# ProProject_New_Project_2023-08-26_19-08-.net
KiCad netlist of a schematic drawn in EasyEDA Pro
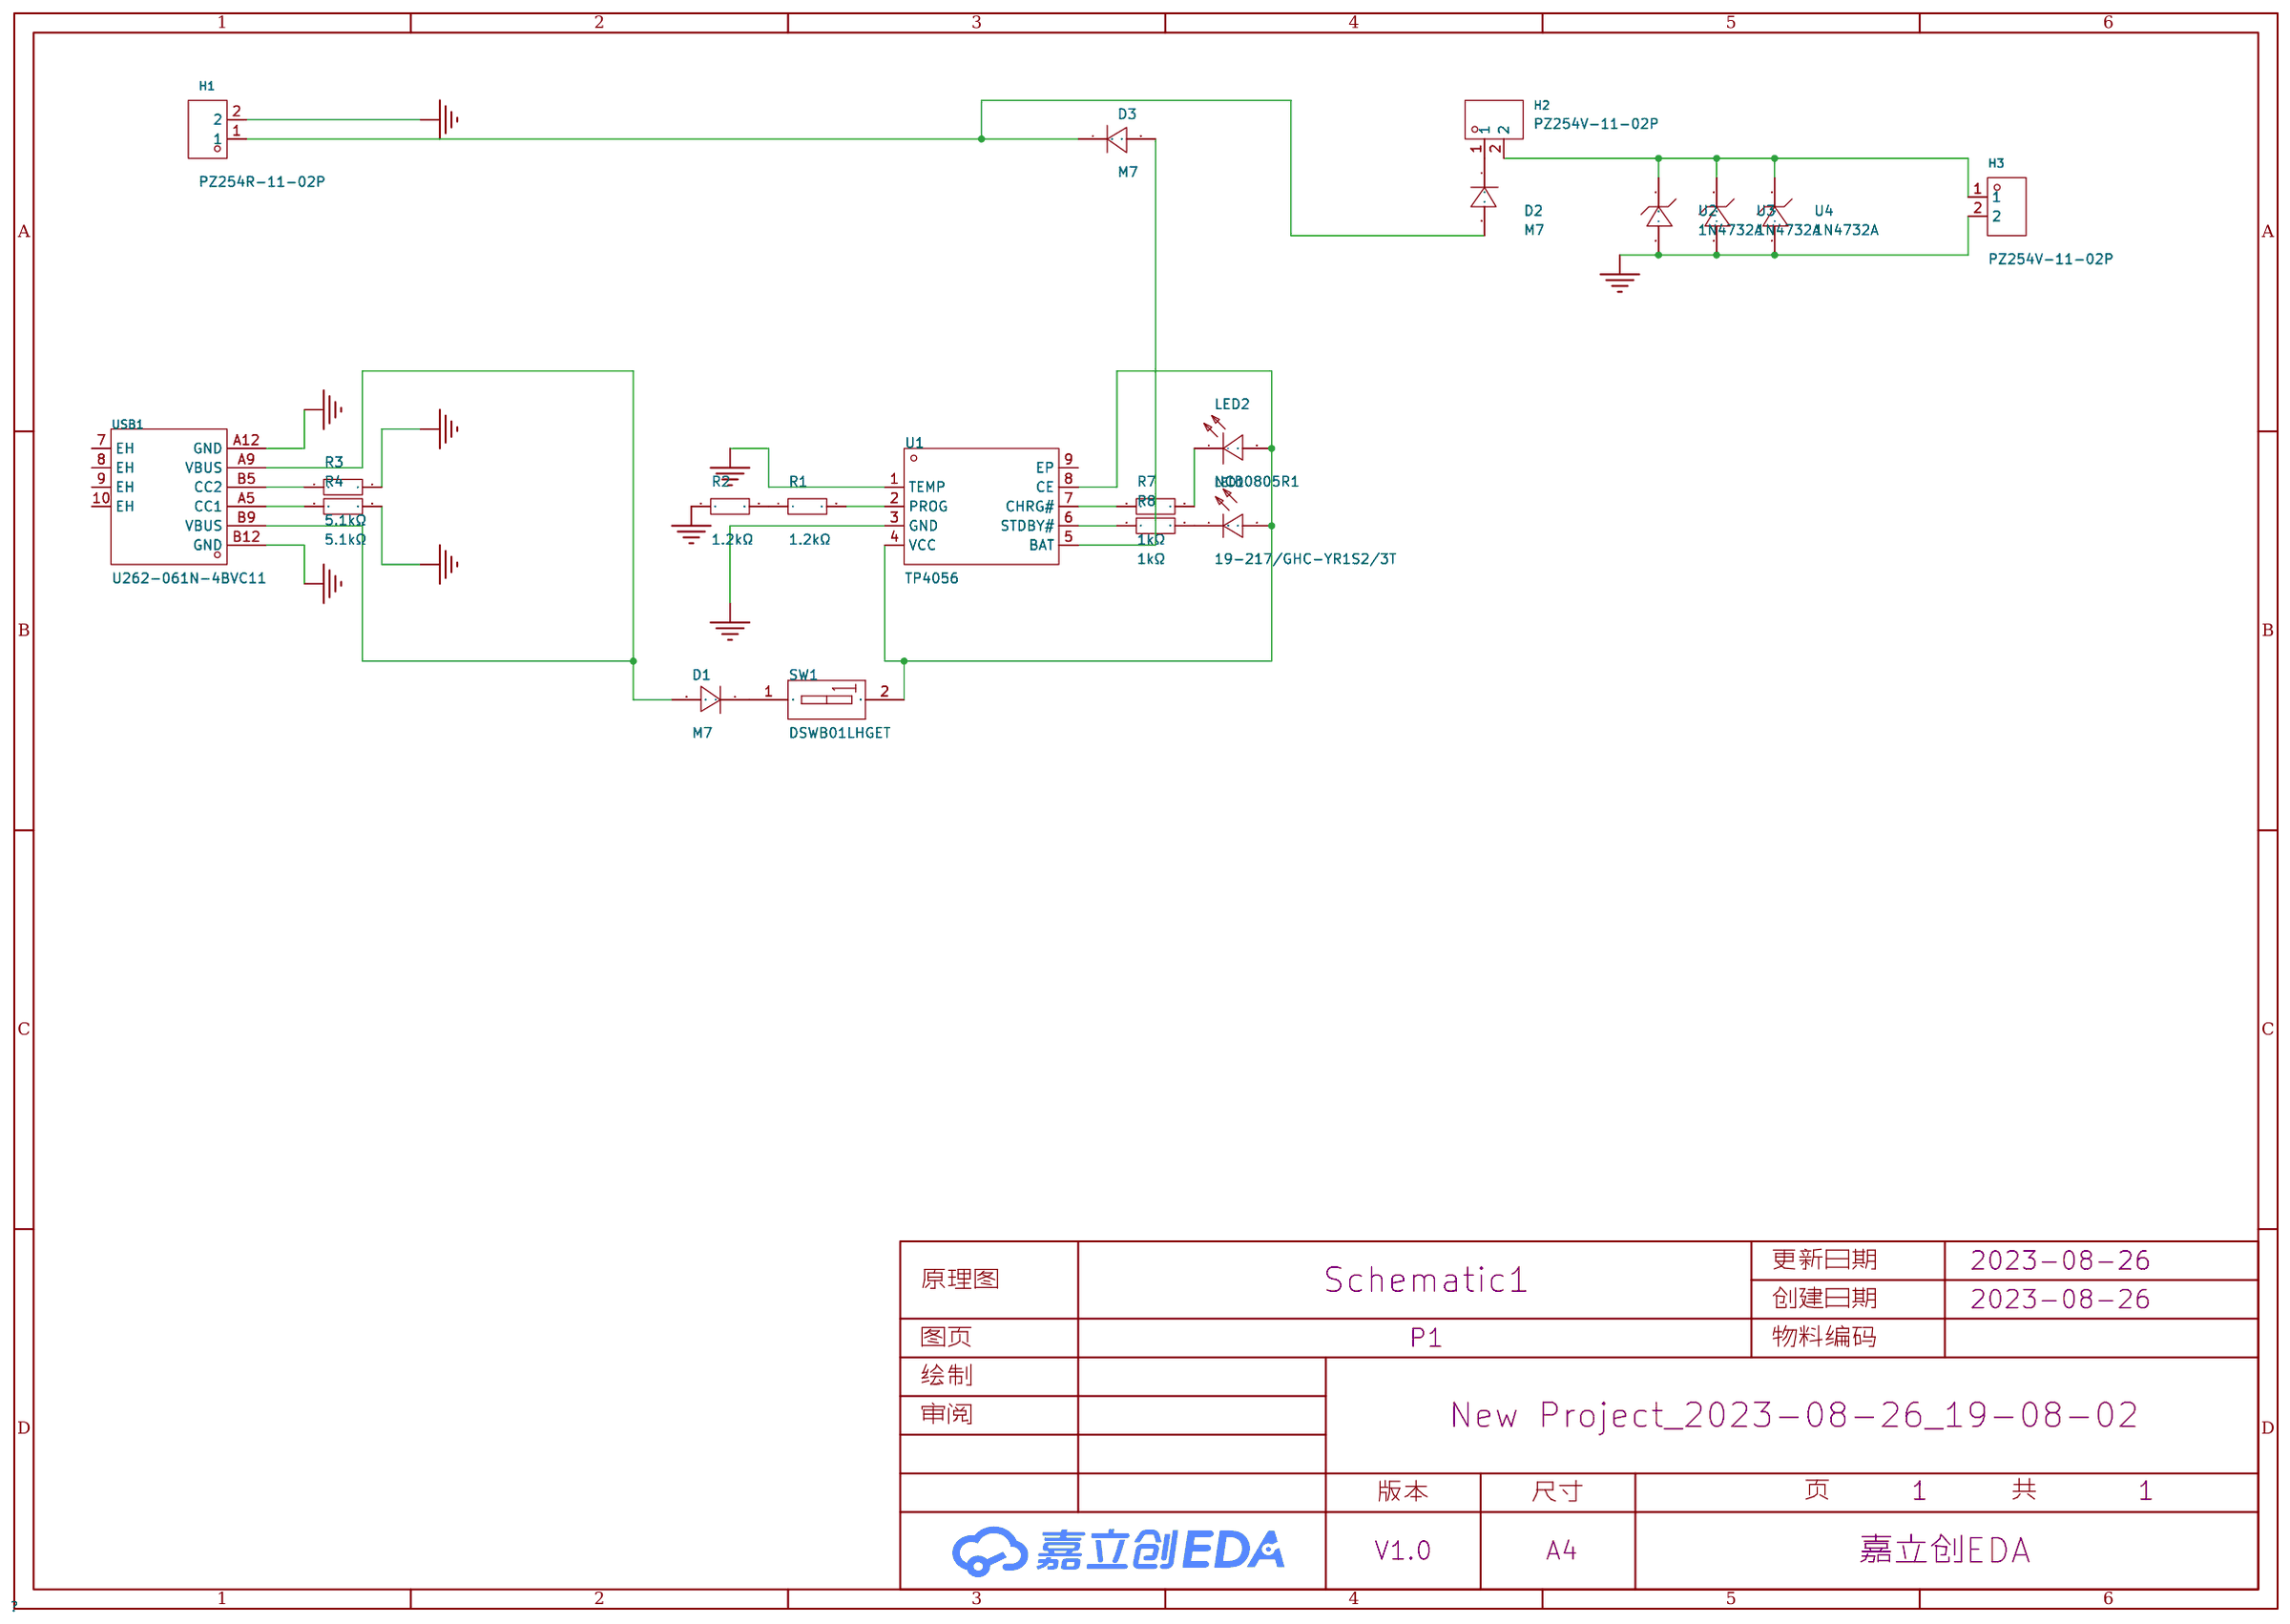
[diagram p0: schematic sheet]

(export (version "E")
  (design (tool "Eeschema 10.0.6"))
  (components
    (comp (ref "D1")
      (value "M7")
      (footprint "easyedapro:SMA_L4.3-W2.6-LS5.2-RD")
      (description "二极管配置:-;直流反向耐压(Vr):1kV;平均整流电流(Io):1A;正向压降(Vf):1.1V@1A;反向电流(Ir):5uA@1kV;")
      (fields (field (name "Manufacturer") "MDD"))
      (libsource (lib "easyedapro") (part "M7_C95872"))
    )
    (comp (ref "D2")
      (value "M7")
      (footprint "easyedapro:SMA_L4.3-W2.6-LS5.2-RD")
      (description "二极管配置:-;直流反向耐压(Vr):1kV;平均整流电流(Io):1A;正向压降(Vf):1.1V@1A;反向电流(Ir):5uA@1kV;")
      (fields (field (name "Manufacturer") "MDD"))
      (libsource (lib "easyedapro") (part "M7_C95872"))
    )
    (comp (ref "D3")
      (value "M7")
      (footprint "easyedapro:SMA_L4.3-W2.6-LS5.2-RD")
      (description "二极管配置:-;直流反向耐压(Vr):1kV;平均整流电流(Io):1A;正向压降(Vf):1.1V@1A;反向电流(Ir):5uA@1kV;")
      (fields (field (name "Manufacturer") "MDD"))
      (libsource (lib "easyedapro") (part "M7_C95872"))
    )
    (comp (ref "H1")
      (value "PZ254R-11-02P")
      (footprint "easyedapro:HDR-TH_2P-P2.54-H-M-W10.4")
      (fields (field (name "Manufacturer") "XFCN(兴飞)"))
      (libsource (lib "easyedapro") (part "PZ254R-11-02P"))
    )
    (comp (ref "H2")
      (value "PZ254V-11-02P")
      (footprint "easyedapro:HDR-TH_2P-P2.54-V-M")
      (fields (field (name "Manufacturer") "XFCN(兴飞)"))
      (libsource (lib "easyedapro") (part "PZ254V-11-02P"))
    )
    (comp (ref "H3")
      (value "PZ254V-11-02P")
      (footprint "easyedapro:HDR-TH_2P-P2.54-V-M")
      (fields (field (name "Manufacturer") "XFCN(兴飞)"))
      (libsource (lib "easyedapro") (part "PZ254V-11-02P"))
    )
    (comp (ref "LED1")
      (value "19-217/GHC-YR1S2/3T")
      (footprint "easyedapro:LED0603-RD")
      (description "发光颜色:翠绿;二极管配置:-;主波长:520nm~535nm;色温:-;功率:110mW;安装方式:-;")
      (fields (field (name "Manufacturer") "EVERLIGHT(亿光)"))
      (libsource (lib "easyedapro") (part "19-217/GHC-YR1S2/3T"))
    )
    (comp (ref "LED2")
      (value "NCD0805R1")
      (footprint "easyedapro:LED0805-RD_RED")
      (description "发光颜色:红灯;")
      (fields (field (name "Manufacturer") "国星光电"))
      (libsource (lib "easyedapro") (part "FC-2012HRK-620D"))
    )
    (comp (ref "R1")
      (value "1.2kΩ")
      (footprint "easyedapro:R0603")
      (description "电阻类型:厚膜电阻;阻值:1.2kΩ;精度:±1%;功率:100mW;")
      (fields
        (field (name "Manufacturer Part") "0603WAF1201T5E")
        (field (name "Manufacturer") "UNI-ROYAL(厚声)")
      )
      (libsource (lib "easyedapro") (part "0603WAF1201T5E"))
    )
    (comp (ref "R2")
      (value "1.2kΩ")
      (footprint "easyedapro:R0603")
      (description "电阻类型:厚膜电阻;阻值:1.2kΩ;精度:±1%;功率:100mW;")
      (fields
        (field (name "Manufacturer Part") "0603WAF1201T5E")
        (field (name "Manufacturer") "UNI-ROYAL(厚声)")
      )
      (libsource (lib "easyedapro") (part "0603WAF1201T5E"))
    )
    (comp (ref "R3")
      (value "5.1kΩ")
      (footprint "easyedapro:R0603")
      (description "电阻类型:厚膜电阻;阻值:5.1kΩ;精度:±1%;功率:100mW;")
      (fields
        (field (name "Manufacturer Part") "0603WAF5101T5E")
        (field (name "Manufacturer") "UNI-ROYAL(厚声)")
      )
      (libsource (lib "easyedapro") (part "0603WAF5101T5E"))
    )
    (comp (ref "R4")
      (value "5.1kΩ")
      (footprint "easyedapro:R0603")
      (description "电阻类型:厚膜电阻;阻值:5.1kΩ;精度:±1%;功率:100mW;")
      (fields
        (field (name "Manufacturer Part") "0603WAF5101T5E")
        (field (name "Manufacturer") "UNI-ROYAL(厚声)")
      )
      (libsource (lib "easyedapro") (part "0603WAF5101T5E"))
    )
    (comp (ref "R7")
      (value "1kΩ")
      (footprint "easyedapro:R0603")
      (description "电阻类型:厚膜电阻;阻值:1kΩ;精度:±1%;功率:100mW;")
      (fields
        (field (name "Manufacturer Part") "0603WAF1001T5E")
        (field (name "Manufacturer") "UNI-ROYAL(厚声)")
      )
      (libsource (lib "easyedapro") (part "0603WAF1001T5E"))
    )
    (comp (ref "R8")
      (value "1kΩ")
      (footprint "easyedapro:R0603")
      (description "电阻类型:厚膜电阻;阻值:1kΩ;精度:±1%;功率:100mW;")
      (fields
        (field (name "Manufacturer Part") "0603WAF1001T5E")
        (field (name "Manufacturer") "UNI-ROYAL(厚声)")
      )
      (libsource (lib "easyedapro") (part "0603WAF1001T5E"))
    )
    (comp (ref "SW1")
      (value "DSWB01LHGET")
      (footprint "easyedapro:SW-TH_DSWB01LHGET")
      (description "类型:平拨,凸起式;电路结构:单刀单掷;开关位数:1;使用寿命:-;颜色:红色;")
      (fields (field (name "Manufacturer") "YE"))
      (libsource (lib "easyedapro") (part "DSWB01LHGET"))
    )
    (comp (ref "U1")
      (value "TP4056")
      (footprint "easyedapro:ESOP-8_L4.9-W3.9-P1.27-LS6.0-BL-EP")
      (fields (field (name "Manufacturer") "UMW(友台半导体)"))
      (libsource (lib "easyedapro") (part "TP4056_C725790"))
    )
    (comp (ref "U2")
      (value "1N4732A")
      (footprint "easyedapro:DO-41_BD2.4-L4.7-P8.70-D0.9-RD")
      (fields (field (name "Manufacturer") "onsemi(安森美)"))
      (libsource (lib "easyedapro") (part "1N4732A_C890042"))
    )
    (comp (ref "U3")
      (value "1N4732A")
      (footprint "easyedapro:DO-41_BD2.4-L4.7-P8.70-D0.9-RD")
      (fields (field (name "Manufacturer") "onsemi(安森美)"))
      (libsource (lib "easyedapro") (part "1N4732A_C890042"))
    )
    (comp (ref "U4")
      (value "1N4732A")
      (footprint "easyedapro:DO-41_BD2.4-L4.7-P8.70-D0.9-RD")
      (fields (field (name "Manufacturer") "onsemi(安森美)"))
      (libsource (lib "easyedapro") (part "1N4732A_C890042"))
    )
    (comp (ref "USB1")
      (value "U262-061N-4BVC11")
      (footprint "easyedapro:USB-SMD_U262-061N-4BVC11")
      (fields (field (name "Manufacturer") "XKB Connectivity(中国星坤)"))
      (libsource (lib "easyedapro") (part "U262-061N-4BVC11"))
    )
  )
  (nets
    (net (code "1") (name "GND") (class "Default")
      (node (ref "H1") (pin "2") (pinfunction "2_2") (pintype "input"))
      (node (ref "H3") (pin "2") (pinfunction "2_2") (pintype "input"))
      (node (ref "R2") (pin "1") (pinfunction "1_1") (pintype "input"))
      (node (ref "R3") (pin "2") (pinfunction "2_2") (pintype "input"))
      (node (ref "R4") (pin "2") (pinfunction "2_2") (pintype "input"))
      (node (ref "U1") (pin "1") (pinfunction "TEMP_1") (pintype "input"))
      (node (ref "U1") (pin "3") (pinfunction "GND_3") (pintype "input"))
      (node (ref "U2") (pin "2") (pinfunction "A_2") (pintype "input"))
      (node (ref "U3") (pin "2") (pinfunction "A_2") (pintype "input"))
      (node (ref "U4") (pin "2") (pinfunction "A_2") (pintype "input"))
      (node (ref "USB1") (pin "A12") (pinfunction "GND_A12") (pintype "input"))
      (node (ref "USB1") (pin "B12") (pinfunction "GND_B12") (pintype "input"))
    )
    (net (code "2") (name "Net-(D1-A)") (class "Default")
      (node (ref "D1") (pin "2") (pinfunction "A_2") (pintype "input"))
      (node (ref "USB1") (pin "A9") (pinfunction "VBUS_A9") (pintype "input"))
      (node (ref "USB1") (pin "B9") (pinfunction "VBUS_B9") (pintype "input"))
    )
    (net (code "3") (name "Net-(D1-K)") (class "Default")
      (node (ref "D1") (pin "1") (pinfunction "K_1") (pintype "input"))
      (node (ref "SW1") (pin "1") (pinfunction "A1_1") (pintype "input"))
    )
    (net (code "4") (name "Net-(D2-A)") (class "Default")
      (node (ref "D2") (pin "2") (pinfunction "A_2") (pintype "input"))
      (node (ref "D3") (pin "1") (pinfunction "K_1") (pintype "input"))
      (node (ref "H1") (pin "1") (pinfunction "1_1") (pintype "input"))
    )
    (net (code "5") (name "Net-(D2-K)") (class "Default")
      (node (ref "D2") (pin "1") (pinfunction "K_1") (pintype "input"))
      (node (ref "H2") (pin "1") (pinfunction "1_1") (pintype "input"))
    )
    (net (code "6") (name "Net-(D3-A)") (class "Default")
      (node (ref "D3") (pin "2") (pinfunction "A_2") (pintype "input"))
      (node (ref "U1") (pin "5") (pinfunction "BAT_5") (pintype "input"))
    )
    (net (code "7") (name "Net-(LED1-A)") (class "Default")
      (node (ref "LED1") (pin "2") (pinfunction "A_2") (pintype "input"))
      (node (ref "LED2") (pin "2") (pinfunction "+_2") (pintype "input"))
      (node (ref "SW1") (pin "2") (pinfunction "2_2") (pintype "input"))
      (node (ref "U1") (pin "4") (pinfunction "VCC_4") (pintype "input"))
      (node (ref "U1") (pin "8") (pinfunction "CE_8") (pintype "input"))
    )
    (net (code "8") (name "Net-(LED1-C)") (class "Default")
      (node (ref "LED1") (pin "1") (pinfunction "C_1") (pintype "input"))
      (node (ref "R8") (pin "2") (pinfunction "2_2") (pintype "input"))
    )
    (net (code "9") (name "Net-(LED2--)") (class "Default")
      (node (ref "LED2") (pin "1") (pinfunction "-_1") (pintype "input"))
      (node (ref "R7") (pin "2") (pinfunction "2_2") (pintype "input"))
    )
    (net (code "10") (name "Net-(R1-Pad1)") (class "Default")
      (node (ref "R1") (pin "1") (pinfunction "1_1") (pintype "input"))
      (node (ref "R2") (pin "2") (pinfunction "2_2") (pintype "input"))
    )
    (net (code "11") (name "Net-(U1-CHRG#)") (class "Default")
      (node (ref "R7") (pin "1") (pinfunction "1_1") (pintype "input"))
      (node (ref "U1") (pin "7") (pinfunction "CHRG#_7") (pintype "input"))
    )
    (net (code "12") (name "Net-(U1-PROG)") (class "Default")
      (node (ref "R1") (pin "2") (pinfunction "2_2") (pintype "input"))
      (node (ref "U1") (pin "2") (pinfunction "PROG_2") (pintype "input"))
    )
    (net (code "13") (name "Net-(U1-STDBY#)") (class "Default")
      (node (ref "R8") (pin "1") (pinfunction "1_1") (pintype "input"))
      (node (ref "U1") (pin "6") (pinfunction "STDBY#_6") (pintype "input"))
    )
    (net (code "14") (name "Net-(U2-C)") (class "Default")
      (node (ref "H2") (pin "2") (pinfunction "2_2") (pintype "input"))
      (node (ref "H3") (pin "1") (pinfunction "1_1") (pintype "input"))
      (node (ref "U2") (pin "1") (pinfunction "C_1") (pintype "input"))
      (node (ref "U3") (pin "1") (pinfunction "C_1") (pintype "input"))
      (node (ref "U4") (pin "1") (pinfunction "C_1") (pintype "input"))
    )
    (net (code "15") (name "Net-(USB1-CC1)") (class "Default")
      (node (ref "R4") (pin "1") (pinfunction "1_1") (pintype "input"))
      (node (ref "USB1") (pin "A5") (pinfunction "CC1_A5") (pintype "input"))
    )
    (net (code "16") (name "Net-(USB1-CC2)") (class "Default")
      (node (ref "R3") (pin "1") (pinfunction "1_1") (pintype "input"))
      (node (ref "USB1") (pin "B5") (pinfunction "CC2_B5") (pintype "input"))
    )
    (net (code "17") (name "unconnected-(U1-EP-Pad9)") (class "Default")
      (node (ref "U1") (pin "9") (pinfunction "EP_9") (pintype "input"))
    )
    (net (code "18") (name "unconnected-(USB1-EH-Pad7)") (class "Default")
      (node (ref "USB1") (pin "7") (pinfunction "EH_7") (pintype "input"))
    )
    (net (code "19") (name "unconnected-(USB1-EH-Pad8)") (class "Default")
      (node (ref "USB1") (pin "8") (pinfunction "EH_8") (pintype "input"))
    )
    (net (code "20") (name "unconnected-(USB1-EH-Pad9)") (class "Default")
      (node (ref "USB1") (pin "9") (pinfunction "EH_9") (pintype "input"))
    )
    (net (code "21") (name "unconnected-(USB1-EH-Pad10)") (class "Default")
      (node (ref "USB1") (pin "10") (pinfunction "EH_10") (pintype "input"))
    )
  )
)
